# Potentiometers_smd_EasyEDA_professional_.net
KiCad netlist of a schematic drawn in EasyEDA Pro
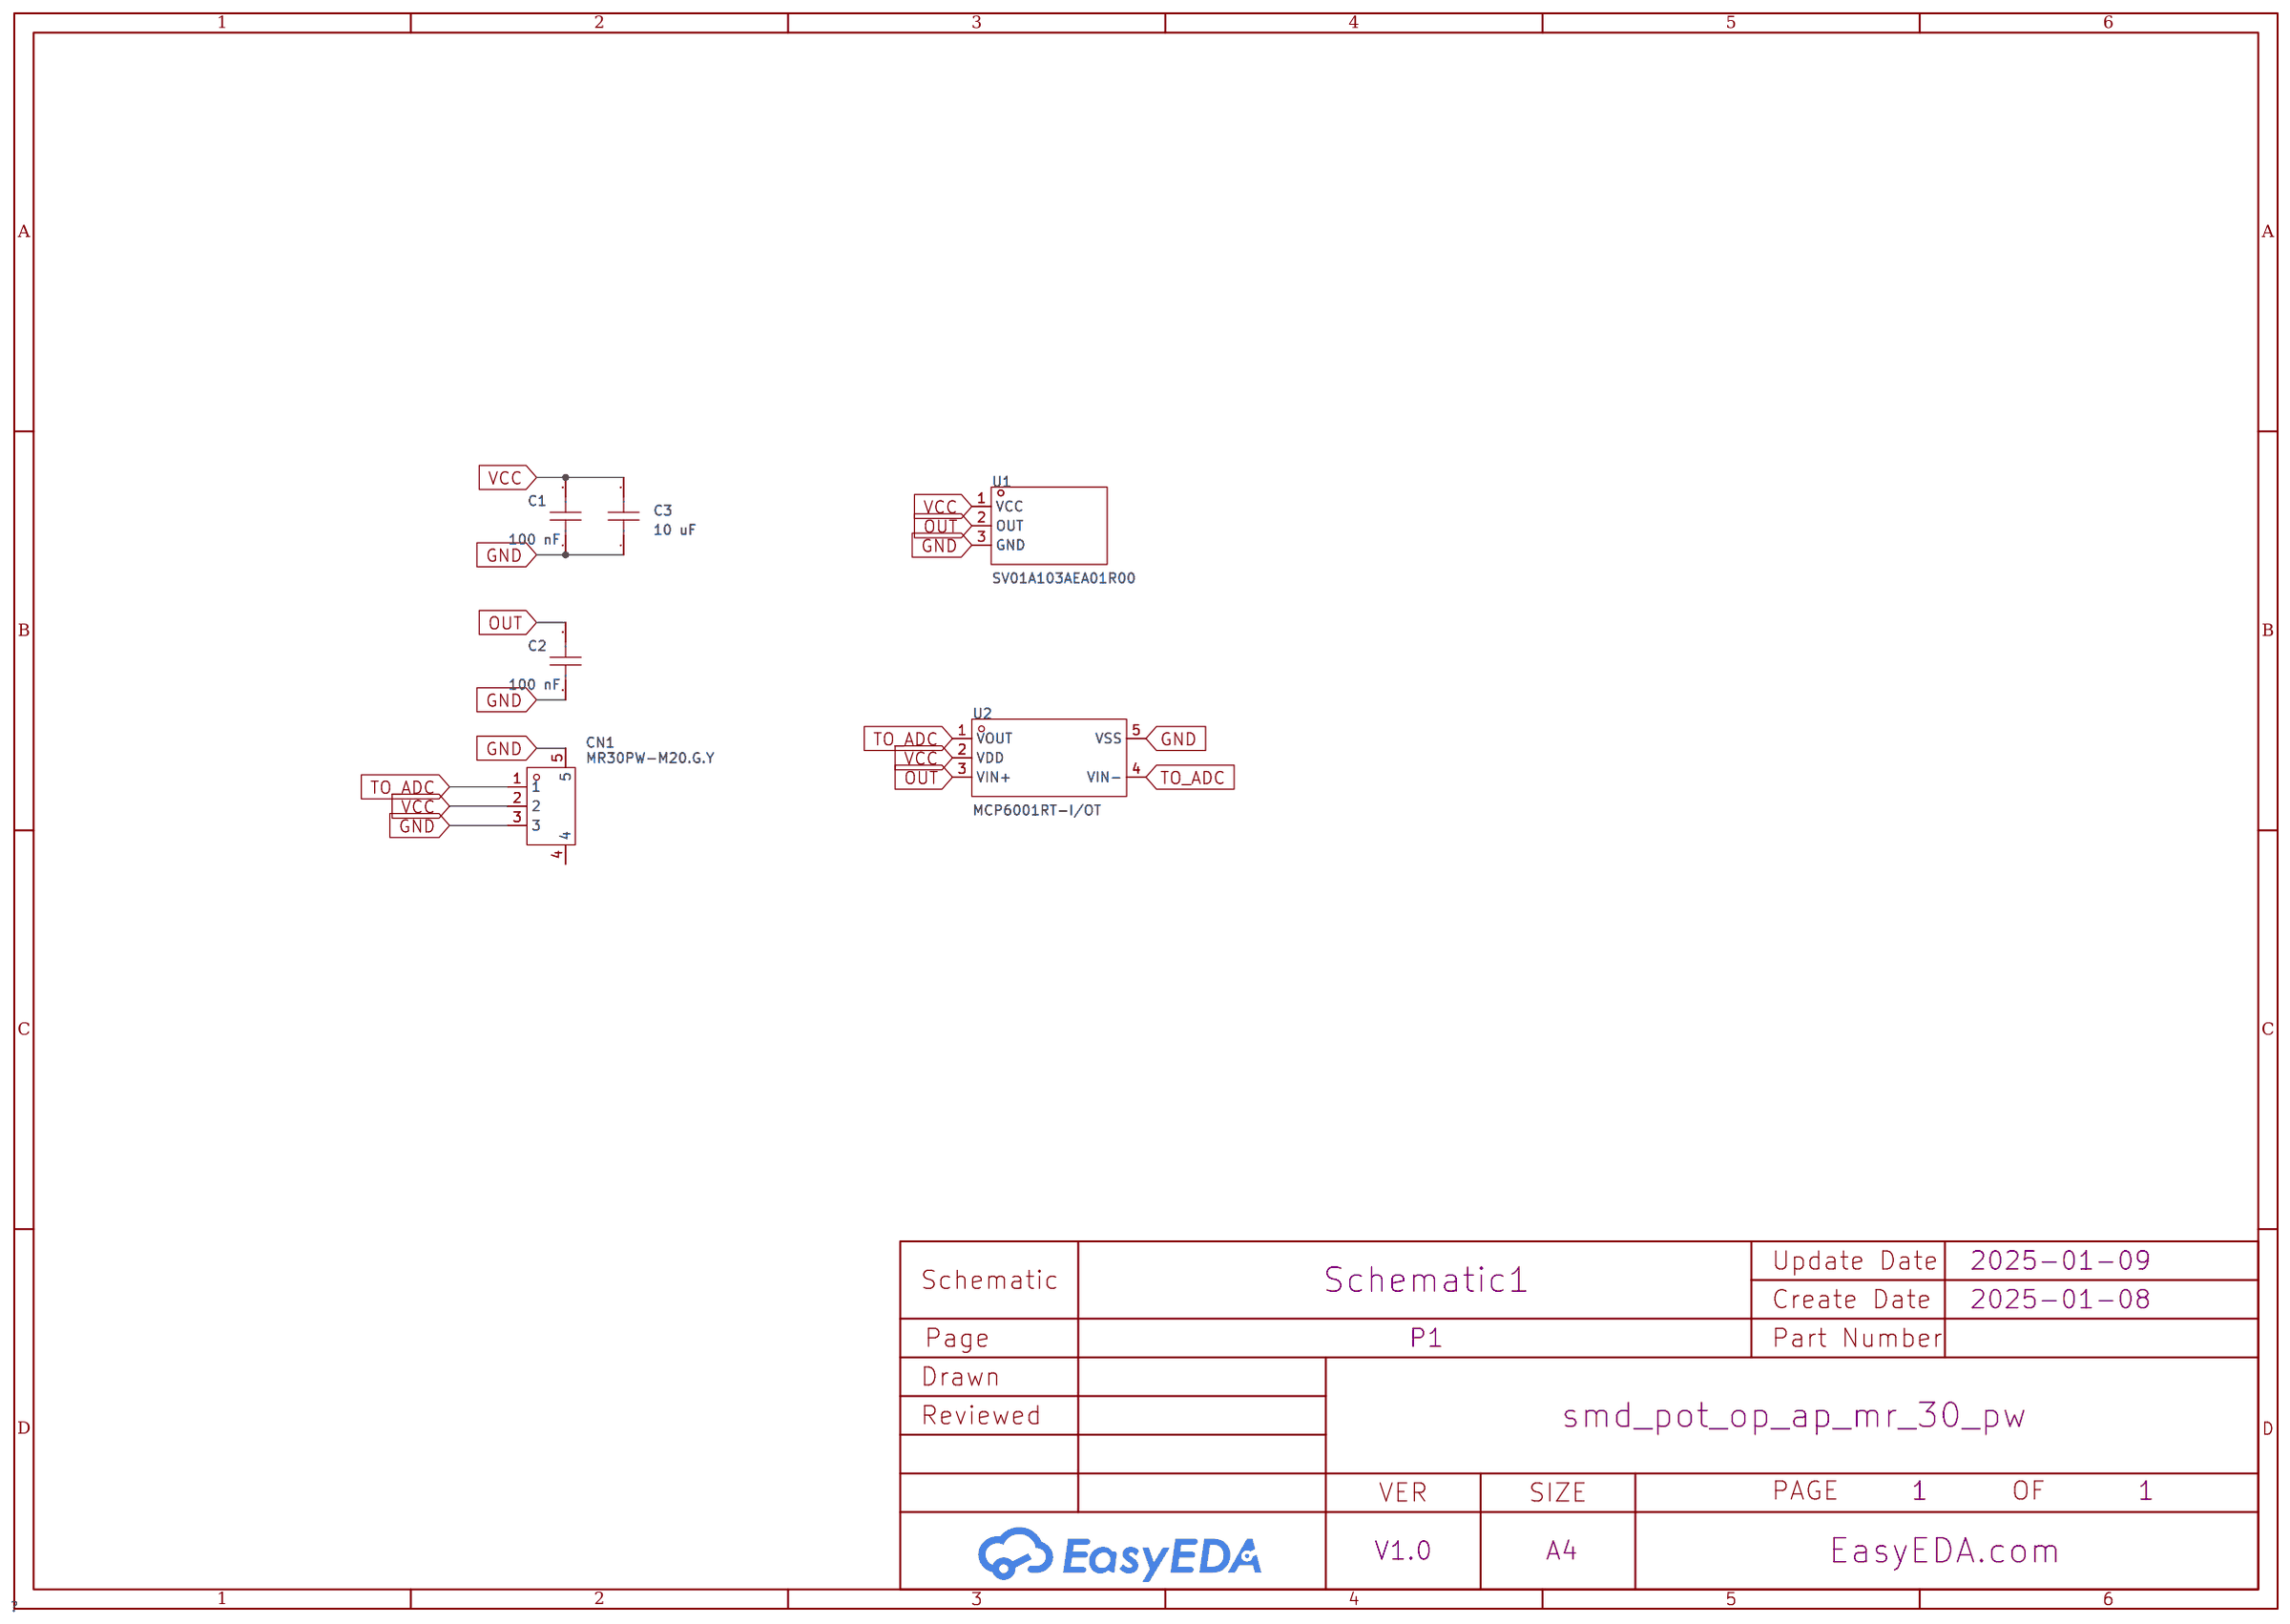
[diagram p0: schematic sheet]

(export (version "E")
  (design (tool "Eeschema 10.0.6"))
  (components
    (comp (ref "C1")
      (value "100 nF")
      (footprint "easyedapro:C0603")
      (libsource (lib "easyedapro") (part "CAP"))
    )
    (comp (ref "C2")
      (value "100 nF")
      (footprint "easyedapro:C0603")
      (libsource (lib "easyedapro") (part "CAP"))
    )
    (comp (ref "C3")
      (value "10 uF")
      (footprint "easyedapro:C0603")
      (libsource (lib "easyedapro") (part "CAP"))
    )
    (comp (ref "CN1")
      (value "MR30PW-M20.G.Y")
      (footprint "easyedapro:CONN-TH_MR30PW-M30-G-Y")
      (fields (field (name "Manufacturer") "AMASS(艾迈斯)"))
      (libsource (lib "easyedapro") (part "MR30PW-M20.G.Y"))
    )
    (comp (ref "U1")
      (value "SV01A103AEA01R00")
      (footprint "easyedapro:SENSOR-SMD_SV01A103AEA01R00")
      (fields (field (name "Manufacturer") "muRata(村田)"))
      (libsource (lib "easyedapro") (part "SV01A103AEA01R00"))
    )
    (comp (ref "U2")
      (value "MCP6001RT-I/OT")
      (footprint "easyedapro:SOT-23-5_L3.0-W1.7-P0.95-LS2.8-BR")
      (fields (field (name "Manufacturer") "MICROCHIP(美国微芯)"))
      (libsource (lib "easyedapro") (part "MCP6001RT-I/OT"))
    )
  )
  (nets
    (net (code "1") (name "GND") (class "Default")
      (node (ref "C1") (pin "1") (pinfunction "1_1") (pintype "input"))
      (node (ref "C2") (pin "1") (pinfunction "1_1") (pintype "input"))
      (node (ref "C3") (pin "1") (pinfunction "1_1") (pintype "input"))
      (node (ref "CN1") (pin "3") (pinfunction "3_3") (pintype "unspecified"))
      (node (ref "CN1") (pin "5") (pinfunction "5_5") (pintype "unspecified"))
      (node (ref "U1") (pin "3") (pinfunction "GND_3") (pintype "unspecified"))
      (node (ref "U2") (pin "5") (pinfunction "VSS_5") (pintype "unspecified"))
    )
    (net (code "2") (name "OUT") (class "Default")
      (node (ref "C2") (pin "2") (pinfunction "2_2") (pintype "input"))
      (node (ref "U1") (pin "2") (pinfunction "OUT_2") (pintype "unspecified"))
      (node (ref "U2") (pin "3") (pinfunction "VIN+_3") (pintype "unspecified"))
    )
    (net (code "3") (name "TO_ADC") (class "Default")
      (node (ref "CN1") (pin "1") (pinfunction "1_1") (pintype "unspecified"))
      (node (ref "U2") (pin "1") (pinfunction "VOUT_1") (pintype "unspecified"))
      (node (ref "U2") (pin "4") (pinfunction "VIN-_4") (pintype "unspecified"))
    )
    (net (code "4") (name "VCC") (class "Default")
      (node (ref "C1") (pin "2") (pinfunction "2_2") (pintype "input"))
      (node (ref "C3") (pin "2") (pinfunction "2_2") (pintype "input"))
      (node (ref "CN1") (pin "2") (pinfunction "2_2") (pintype "unspecified"))
      (node (ref "U1") (pin "1") (pinfunction "VCC_1") (pintype "unspecified"))
      (node (ref "U2") (pin "2") (pinfunction "VDD_2") (pintype "unspecified"))
    )
    (net (code "5") (name "unconnected-(CN1-Pad4)") (class "Default")
      (node (ref "CN1") (pin "4") (pinfunction "4_4") (pintype "unspecified"))
    )
  )
)
